# RTC.net
KiCad netlist of a schematic drawn in Altium Designer
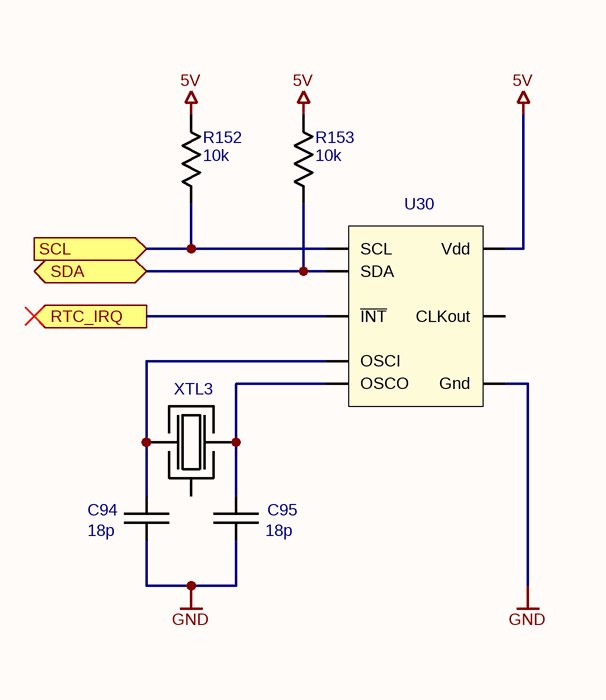
[diagram p0: RTC.SchDoc]

(export (version "E")
  (design (tool "Eeschema 10.0.6"))
  (components
    (comp (ref "C94")
      (value "18p")
      (footprint "levin:CAP CER 0603 NP")
      (description "CC0603JRNPO9BN180")
      (libsource (lib "levin") (part "Capacitor"))
    )
    (comp (ref "C95")
      (value "18p")
      (footprint "levin:CAP CER 0603 NP")
      (description "CC0603JRNPO9BN180")
      (libsource (lib "levin") (part "Capacitor"))
    )
    (comp (ref "R152")
      (value "10k")
      (footprint "levin:RES 0603")
      (description "RC0603FR-0710KL")
      (libsource (lib "levin") (part "Resistor"))
    )
    (comp (ref "R153")
      (value "10k")
      (footprint "levin:RES 0603")
      (description "RC0603FR-0710KL")
      (libsource (lib "levin") (part "Resistor"))
    )
    (comp (ref "U30")
      (value "Real-Time Clock IC")
      (footprint "levin:SOIC-8")
      (description "PCF8563T/5,518")
      (libsource (lib "levin") (part "PCF8653"))
    )
    (comp (ref "XTL3")
      (value "32.768 kHz")
      (footprint "levin:XTAL KX-327NHT")
      (description "12.87150")
      (libsource (lib "levin") (part "Quartz Resonator"))
    )
  )
  (nets
    (net (code "1") (name "/RTC_IRQ") (class "Default")
      (node (ref "U30") (pin "3") (pinfunction "~{INT}_3") (pintype "passive"))
    )
    (net (code "2") (name "/SCL") (class "Default")
      (node (ref "R152") (pin "1") (pinfunction "1_1") (pintype "passive"))
      (node (ref "U30") (pin "6") (pinfunction "SCL_6") (pintype "passive"))
    )
    (net (code "3") (name "/SDA") (class "Default")
      (node (ref "R153") (pin "1") (pinfunction "1_1") (pintype "passive"))
      (node (ref "U30") (pin "5") (pinfunction "SDA_5") (pintype "passive"))
    )
    (net (code "4") (name "5V") (class "Default")
      (node (ref "R152") (pin "2") (pinfunction "2_2") (pintype "passive"))
      (node (ref "R153") (pin "2") (pinfunction "2_2") (pintype "passive"))
      (node (ref "U30") (pin "8") (pinfunction "Vdd_8") (pintype "passive"))
    )
    (net (code "5") (name "GND") (class "Default")
      (node (ref "C94") (pin "1") (pinfunction "1_1") (pintype "passive"))
      (node (ref "C95") (pin "1") (pinfunction "1_1") (pintype "passive"))
      (node (ref "U30") (pin "4") (pinfunction "Gnd_4") (pintype "passive"))
    )
    (net (code "6") (name "Net-(U30-OSCI)") (class "Default")
      (node (ref "C94") (pin "2") (pinfunction "2_2") (pintype "passive"))
      (node (ref "U30") (pin "1") (pinfunction "OSCI_1") (pintype "passive"))
      (node (ref "XTL3") (pin "1") (pinfunction "1_1") (pintype "passive"))
    )
    (net (code "7") (name "Net-(U30-OSCO)") (class "Default")
      (node (ref "C95") (pin "2") (pinfunction "2_2") (pintype "passive"))
      (node (ref "U30") (pin "2") (pinfunction "OSCO_2") (pintype "passive"))
      (node (ref "XTL3") (pin "3") (pinfunction "3_3") (pintype "passive"))
    )
    (net (code "8") (name "unconnected-(U30-CLKout-Pad7)") (class "Default")
      (node (ref "U30") (pin "7") (pinfunction "CLKout_7") (pintype "passive"))
    )
    (net (code "9") (name "unconnected-(XTL3-Pad2)") (class "Default")
      (node (ref "XTL3") (pin "2") (pinfunction "2_2") (pintype "passive"))
    )
  )
)
